# 2225B_VumetreFrequenciel.net
KiCad netlist of a schematic drawn in Altium Designer
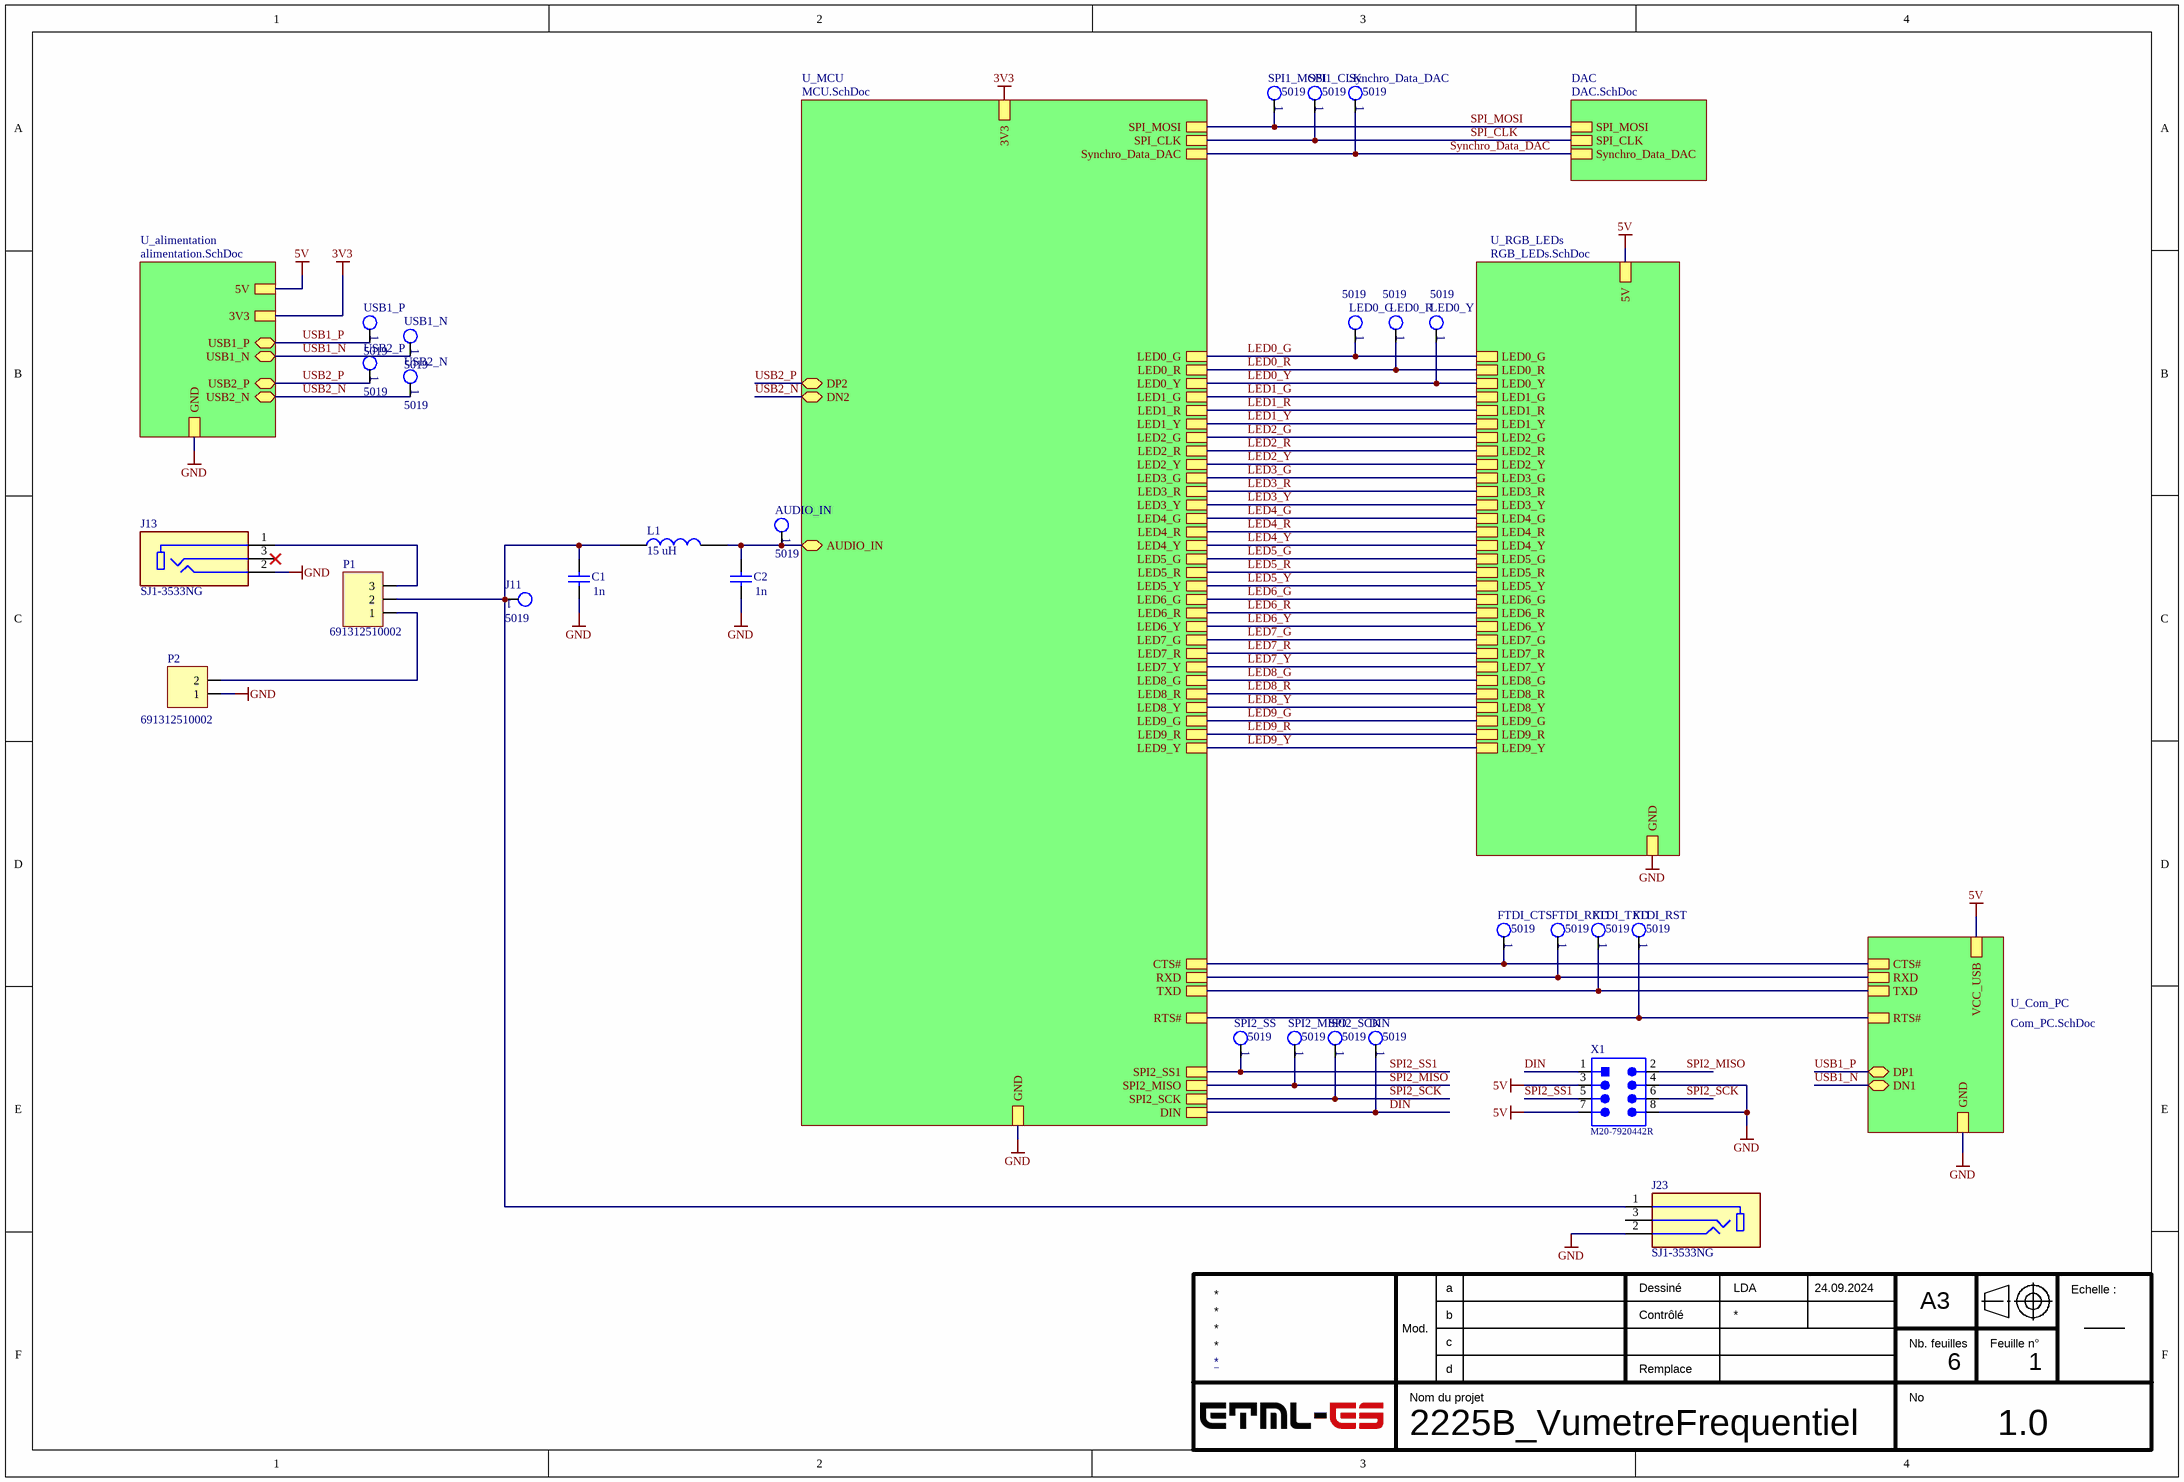
[diagram p0: 2225B_VumetreFrequenciel.SchDoc]

(export (version "E")
  (design (tool "Eeschema 10.0.6"))
  (components
    (comp (ref "AUDIO_IN")
      (value "5019")
      (footprint "KEYSTONE_5019")
      (fields (field (name "MANUFACTURER") "Keystone Electronics"))
      (libsource (lib "2225B_VumetreFrequenciel") (part "CMP-1672-00008-2"))
    )
    (comp (ref "C1")
      (value "1n")
      (footprint "C0805")
      (description "Capacitor")
      (fields (field (name "PUBLISHER") "Altium Limited"))
      (libsource (lib "Miscellaneous Devices") (part "Cap"))
    )
    (comp (ref "C2")
      (value "1n")
      (footprint "C0805")
      (description "Capacitor")
      (fields (field (name "PUBLISHER") "Altium Limited"))
      (libsource (lib "Miscellaneous Devices") (part "Cap"))
    )
    (comp (ref "DIN")
      (value "5019")
      (footprint "KEYSTONE_5019")
      (fields (field (name "MANUFACTURER") "Keystone Electronics"))
      (libsource (lib "2225B_VumetreFrequenciel") (part "CMP-1672-00008-2"))
    )
    (comp (ref "FTDI_CTS")
      (value "5019")
      (footprint "KEYSTONE_5019")
      (fields (field (name "MANUFACTURER") "Keystone Electronics"))
      (libsource (lib "2225B_VumetreFrequenciel") (part "CMP-1672-00008-2"))
    )
    (comp (ref "FTDI_RST")
      (value "5019")
      (footprint "KEYSTONE_5019")
      (fields (field (name "MANUFACTURER") "Keystone Electronics"))
      (libsource (lib "2225B_VumetreFrequenciel") (part "CMP-1672-00008-2"))
    )
    (comp (ref "FTDI_RXD")
      (value "5019")
      (footprint "KEYSTONE_5019")
      (fields (field (name "MANUFACTURER") "Keystone Electronics"))
      (libsource (lib "2225B_VumetreFrequenciel") (part "CMP-1672-00008-2"))
    )
    (comp (ref "FTDI_TXD")
      (value "5019")
      (footprint "KEYSTONE_5019")
      (fields (field (name "MANUFACTURER") "Keystone Electronics"))
      (libsource (lib "2225B_VumetreFrequenciel") (part "CMP-1672-00008-2"))
    )
    (comp (ref "J11")
      (value "5019")
      (footprint "KEYSTONE_5019")
      (fields (field (name "MANUFACTURER") "Keystone Electronics"))
      (libsource (lib "2225B_VumetreFrequenciel") (part "CMP-1672-00008-2"))
    )
    (comp (ref "J13")
      (value "SJ1-3533NG")
      (footprint "CUI_SJ1-3533NG")
      (description "3.5 mm Right-Angle Stereo Jack, 3 Pin PCB Mount, Isolated Ground")
      (fields (field (name "MF") "{'manufacturer': u'CUI'}"))
      (libsource (lib "2227_BoiteBruitage") (part "SJ1-3533NG"))
    )
    (comp (ref "J23")
      (value "SJ1-3533NG")
      (footprint "CUI_SJ1-3533NG")
      (description "3.5 mm Right-Angle Stereo Jack, 3 Pin PCB Mount, Isolated Ground")
      (fields (field (name "MF") "{'manufacturer': u'CUI'}"))
      (libsource (lib "") (part "SJ1-3533NG_1"))
    )
    (comp (ref "L1")
      (value "15 uH")
      (footprint "WE-PD_1210")
      (description "Fixed Inductors 22uH 2.80A 0.028ohms")
      (fields (field (name "MANUFACTURER_PART_NUMBER") "CDRH125NP-220MC"))
      (libsource (lib "TP2_Convertisseur_Courant") (part "CDRH125NP-220MC"))
    )
    (comp (ref "LED0_G")
      (value "5019")
      (footprint "KEYSTONE_5019")
      (fields (field (name "MANUFACTURER") "Keystone Electronics"))
      (libsource (lib "2225B_VumetreFrequenciel") (part "CMP-1672-00008-2"))
    )
    (comp (ref "LED0_R")
      (value "5019")
      (footprint "KEYSTONE_5019")
      (fields (field (name "MANUFACTURER") "Keystone Electronics"))
      (libsource (lib "2225B_VumetreFrequenciel") (part "CMP-1672-00008-2"))
    )
    (comp (ref "LED0_Y")
      (value "5019")
      (footprint "KEYSTONE_5019")
      (fields (field (name "MANUFACTURER") "Keystone Electronics"))
      (libsource (lib "2225B_VumetreFrequenciel") (part "CMP-1672-00008-2"))
    )
    (comp (ref "P1")
      (value "691312510002")
      (footprint "61300311121")
      (description "Header, 3-Pin")
      (fields (field (name "PUBLISHER") "Altium Limited"))
      (libsource (lib "2225B_VumetreFrequenciel") (part "MHDR1X3"))
    )
    (comp (ref "P2")
      (value "691312510002")
      (footprint "LINX_CONBNC002")
      (description "Header, 2-Pin")
      (fields (field (name "PUBLISHER") "Altium Limited"))
      (libsource (lib "2225B_VumetreFrequenciel") (part "MHDR1X2"))
    )
    (comp (ref "SPI1_CLK")
      (value "5019")
      (footprint "KEYSTONE_5019")
      (fields (field (name "MANUFACTURER") "Keystone Electronics"))
      (libsource (lib "2225B_VumetreFrequenciel") (part "CMP-1672-00008-2"))
    )
    (comp (ref "SPI1_MOSI")
      (value "5019")
      (footprint "KEYSTONE_5019")
      (fields (field (name "MANUFACTURER") "Keystone Electronics"))
      (libsource (lib "2225B_VumetreFrequenciel") (part "CMP-1672-00008-2"))
    )
    (comp (ref "SPI2_MISO")
      (value "5019")
      (footprint "KEYSTONE_5019")
      (fields (field (name "MANUFACTURER") "Keystone Electronics"))
      (libsource (lib "2225B_VumetreFrequenciel") (part "CMP-1672-00008-2"))
    )
    (comp (ref "SPI2_SCK")
      (value "5019")
      (footprint "KEYSTONE_5019")
      (fields (field (name "MANUFACTURER") "Keystone Electronics"))
      (libsource (lib "2225B_VumetreFrequenciel") (part "CMP-1672-00008-2"))
    )
    (comp (ref "SPI2_SS")
      (value "5019")
      (footprint "KEYSTONE_5019")
      (fields (field (name "MANUFACTURER") "Keystone Electronics"))
      (libsource (lib "2225B_VumetreFrequenciel") (part "CMP-1672-00008-2"))
    )
    (comp (ref "Synchro_Data_DAC")
      (value "5019")
      (footprint "KEYSTONE_5019")
      (fields (field (name "MANUFACTURER") "Keystone Electronics"))
      (libsource (lib "2225B_VumetreFrequenciel") (part "CMP-1672-00008-2"))
    )
    (comp (ref "USB1_N")
      (value "5019")
      (footprint "KEYSTONE_5019")
      (fields (field (name "MANUFACTURER") "Keystone Electronics"))
      (libsource (lib "2225B_VumetreFrequenciel") (part "CMP-1672-00008-2"))
    )
    (comp (ref "USB1_P")
      (value "5019")
      (footprint "KEYSTONE_5019")
      (fields (field (name "MANUFACTURER") "Keystone Electronics"))
      (libsource (lib "2225B_VumetreFrequenciel") (part "CMP-1672-00008-2"))
    )
    (comp (ref "USB2_N")
      (value "5019")
      (footprint "KEYSTONE_5019")
      (fields (field (name "MANUFACTURER") "Keystone Electronics"))
      (libsource (lib "2225B_VumetreFrequenciel") (part "CMP-1672-00008-2"))
    )
    (comp (ref "USB2_P")
      (value "5019")
      (footprint "KEYSTONE_5019")
      (fields (field (name "MANUFACTURER") "Keystone Electronics"))
      (libsource (lib "2225B_VumetreFrequenciel") (part "CMP-1672-00008-2"))
    )
    (comp (ref "X1")
      (value "M20-7920442R")
      (footprint "610108249121")
      (description "WR-PHD Pin Header, THT, pitch 2.54mm, Dual Row, Angled, 8p")
      (fields
        (field (name "MANUFACTURER PART NUMBER") "61300821021")
        (field (name "MANUFACTURER") "Wurth Elektronik")
      )
      (libsource (lib "2126_AffichageMatriciel") (part "610108249121"))
    )
  )
  (nets
    (net (code "1") (name "/AUDIO_IN") (class "Default")
      (node (ref "AUDIO_IN") (pin "1") (pinfunction "1_1") (pintype "passive"))
      (node (ref "C2") (pin "1") (pinfunction "1_1") (pintype "passive"))
      (node (ref "L1") (pin "2") (pinfunction "2_2") (pintype "passive"))
    )
    (net (code "2") (name "/CTS#") (class "Default")
      (node (ref "FTDI_CTS") (pin "1") (pinfunction "1_1") (pintype "passive"))
    )
    (net (code "3") (name "/DIN") (class "Default")
      (node (ref "DIN") (pin "1") (pinfunction "1_1") (pintype "passive"))
      (node (ref "X1") (pin "1") (pinfunction "1_1") (pintype "passive"))
    )
    (net (code "4") (name "/LED0_G") (class "Default")
      (node (ref "LED0_G") (pin "1") (pinfunction "1_1") (pintype "passive"))
    )
    (net (code "5") (name "/LED0_R") (class "Default")
      (node (ref "LED0_R") (pin "1") (pinfunction "1_1") (pintype "passive"))
    )
    (net (code "6") (name "/LED0_Y") (class "Default")
      (node (ref "LED0_Y") (pin "1") (pinfunction "1_1") (pintype "passive"))
    )
    (net (code "34") (name "/RTS#") (class "Default")
      (node (ref "FTDI_RST") (pin "1") (pinfunction "1_1") (pintype "passive"))
    )
    (net (code "35") (name "/RXD") (class "Default")
      (node (ref "FTDI_RXD") (pin "1") (pinfunction "1_1") (pintype "passive"))
    )
    (net (code "36") (name "/SPI2_MISO") (class "Default")
      (node (ref "SPI2_MISO") (pin "1") (pinfunction "1_1") (pintype "passive"))
      (node (ref "X1") (pin "2") (pinfunction "2_2") (pintype "passive"))
    )
    (net (code "37") (name "/SPI2_SCK") (class "Default")
      (node (ref "SPI2_SCK") (pin "1") (pinfunction "1_1") (pintype "passive"))
      (node (ref "X1") (pin "6") (pinfunction "6_6") (pintype "passive"))
    )
    (net (code "38") (name "/SPI2_SS1") (class "Default")
      (node (ref "SPI2_SS") (pin "1") (pinfunction "1_1") (pintype "passive"))
      (node (ref "X1") (pin "5") (pinfunction "5_5") (pintype "passive"))
    )
    (net (code "39") (name "/SPI_CLK") (class "Default")
      (node (ref "SPI1_CLK") (pin "1") (pinfunction "1_1") (pintype "passive"))
    )
    (net (code "40") (name "/SPI_MOSI") (class "Default")
      (node (ref "SPI1_MOSI") (pin "1") (pinfunction "1_1") (pintype "passive"))
    )
    (net (code "41") (name "/Synchro_Data_DAC") (class "Default")
      (node (ref "Synchro_Data_DAC") (pin "1") (pinfunction "1_1") (pintype "passive"))
    )
    (net (code "42") (name "/TXD") (class "Default")
      (node (ref "FTDI_TXD") (pin "1") (pinfunction "1_1") (pintype "passive"))
    )
    (net (code "43") (name "/USB1_N") (class "Default")
      (node (ref "USB1_N") (pin "1") (pinfunction "1_1") (pintype "passive"))
    )
    (net (code "44") (name "/USB1_P") (class "Default")
      (node (ref "USB1_P") (pin "1") (pinfunction "1_1") (pintype "passive"))
    )
    (net (code "45") (name "/USB2_N") (class "Default")
      (node (ref "USB2_N") (pin "1") (pinfunction "1_1") (pintype "passive"))
    )
    (net (code "46") (name "/USB2_P") (class "Default")
      (node (ref "USB2_P") (pin "1") (pinfunction "1_1") (pintype "passive"))
    )
    (net (code "48") (name "5V") (class "Default")
      (node (ref "X1") (pin "3") (pinfunction "3_3") (pintype "passive"))
      (node (ref "X1") (pin "7") (pinfunction "7_7") (pintype "passive"))
    )
    (net (code "49") (name "GND") (class "Default")
      (node (ref "C1") (pin "2") (pinfunction "2_2") (pintype "passive"))
      (node (ref "C2") (pin "2") (pinfunction "2_2") (pintype "passive"))
      (node (ref "J13") (pin "2") (pinfunction "2_2") (pintype "passive"))
      (node (ref "J23") (pin "2") (pinfunction "2_2") (pintype "passive"))
      (node (ref "P2") (pin "1") (pinfunction "1_1") (pintype "passive"))
      (node (ref "X1") (pin "4") (pinfunction "4_4") (pintype "passive"))
      (node (ref "X1") (pin "8") (pinfunction "8_8") (pintype "passive"))
    )
    (net (code "50") (name "Net-(C1-Pad1)") (class "Default")
      (node (ref "C1") (pin "1") (pinfunction "1_1") (pintype "passive"))
      (node (ref "J11") (pin "1") (pinfunction "1_1") (pintype "passive"))
      (node (ref "J23") (pin "1") (pinfunction "1_1") (pintype "passive"))
      (node (ref "L1") (pin "1") (pinfunction "1_1") (pintype "passive"))
      (node (ref "P1") (pin "2") (pinfunction "2_2") (pintype "passive"))
    )
    (net (code "51") (name "Net-(J13-Pad1)") (class "Default")
      (node (ref "J13") (pin "1") (pinfunction "1_1") (pintype "passive"))
      (node (ref "P1") (pin "3") (pinfunction "3_3") (pintype "passive"))
    )
    (net (code "52") (name "Net-(P1-Pad1)") (class "Default")
      (node (ref "P1") (pin "1") (pinfunction "1_1") (pintype "passive"))
      (node (ref "P2") (pin "2") (pinfunction "2_2") (pintype "passive"))
    )
    (net (code "53") (name "unconnected-(J13-Pad3)") (class "Default")
      (node (ref "J13") (pin "3") (pinfunction "3_3") (pintype "passive+no_connect"))
    )
    (net (code "54") (name "unconnected-(J23-Pad3)") (class "Default")
      (node (ref "J23") (pin "3") (pinfunction "3_3") (pintype "passive"))
    )
  )
)
